# D1MiniTerminalBoard2Sided.net
KiCad netlist of a schematic drawn in EAGLE
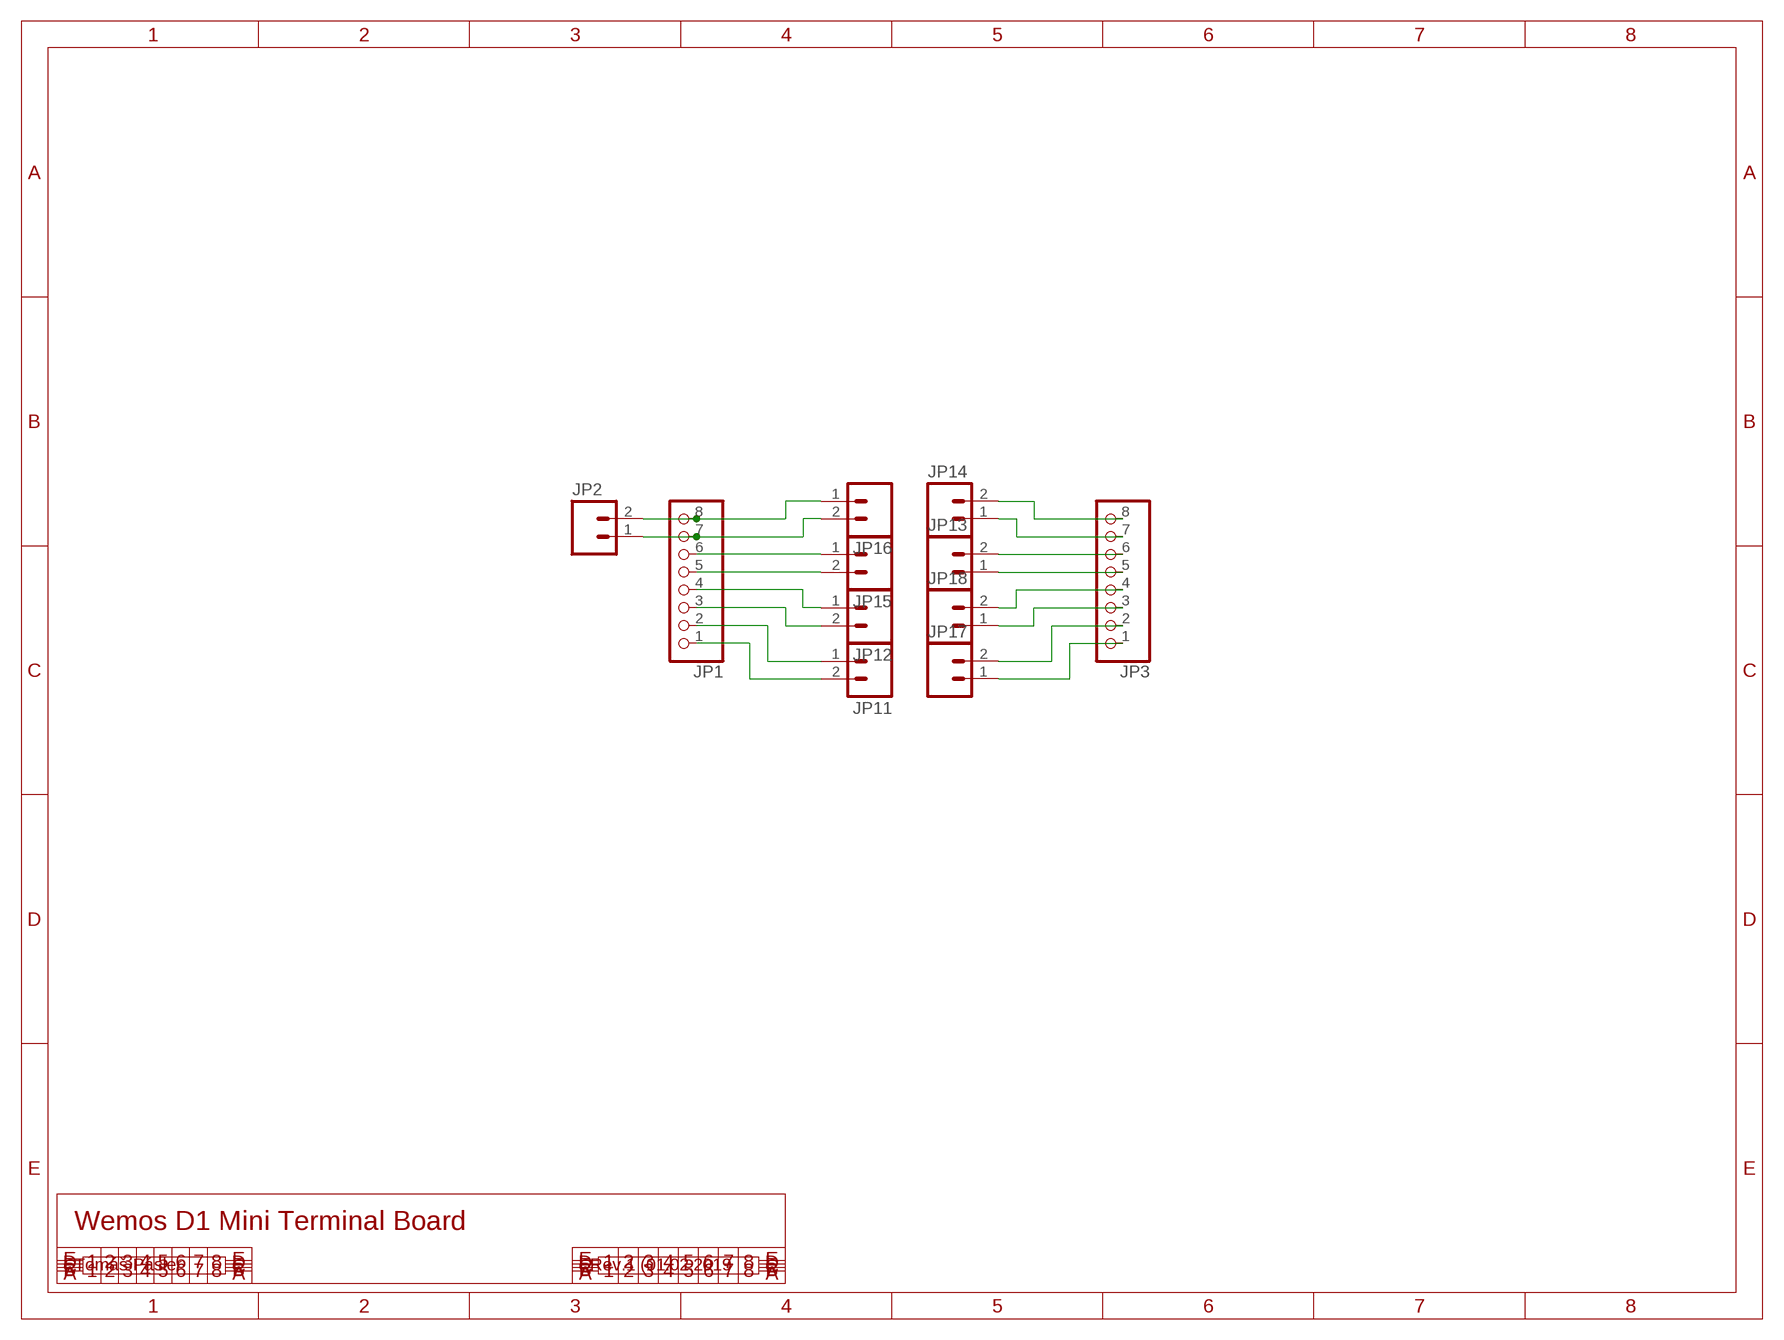
[diagram p0: schematic, sheet 1]

(export (version "E")
  (design (tool "Eeschema 10.0.6"))
  (components
    (comp (ref "JP1")
      (value "PINHD-1X8")
      (footprint "eagle-import:1X08")
      (libsource (lib "eagle-import") (part "PINHD-1X8"))
    )
    (comp (ref "JP2")
      (value "M023.5MM")
      (footprint "eagle-import:SCREWTERMINAL-3.5MM-2")
      (libsource (lib "eagle-import") (part "M023.5MM"))
    )
    (comp (ref "JP3")
      (value "PINHD-1X8")
      (footprint "eagle-import:1X08")
      (libsource (lib "eagle-import") (part "PINHD-1X8"))
    )
    (comp (ref "JP11")
      (value "M023.5MM")
      (footprint "eagle-import:SCREWTERMINAL-3.5MM-2")
      (libsource (lib "eagle-import") (part "M023.5MM"))
    )
    (comp (ref "JP12")
      (value "M023.5MM")
      (footprint "eagle-import:SCREWTERMINAL-3.5MM-2")
      (libsource (lib "eagle-import") (part "M023.5MM"))
    )
    (comp (ref "JP13")
      (value "M023.5MM")
      (footprint "eagle-import:SCREWTERMINAL-3.5MM-2")
      (libsource (lib "eagle-import") (part "M023.5MM"))
    )
    (comp (ref "JP14")
      (value "M023.5MM")
      (footprint "eagle-import:SCREWTERMINAL-3.5MM-2")
      (libsource (lib "eagle-import") (part "M023.5MM"))
    )
    (comp (ref "JP15")
      (value "M023.5MM")
      (footprint "eagle-import:SCREWTERMINAL-3.5MM-2")
      (libsource (lib "eagle-import") (part "M023.5MM"))
    )
    (comp (ref "JP16")
      (value "M023.5MM")
      (footprint "eagle-import:SCREWTERMINAL-3.5MM-2")
      (libsource (lib "eagle-import") (part "M023.5MM"))
    )
    (comp (ref "JP17")
      (value "M023.5MM")
      (footprint "eagle-import:SCREWTERMINAL-3.5MM-2")
      (libsource (lib "eagle-import") (part "M023.5MM"))
    )
    (comp (ref "JP18")
      (value "M023.5MM")
      (footprint "eagle-import:SCREWTERMINAL-3.5MM-2")
      (libsource (lib "eagle-import") (part "M023.5MM"))
    )
  )
  (nets
    (net (code "1") (name "Net-(JP1-Pad1)") (class "Default")
      (node (ref "JP1") (pin "1") (pinfunction "1_1") (pintype "passive"))
      (node (ref "JP11") (pin "2") (pinfunction "2_2") (pintype "passive"))
    )
    (net (code "2") (name "Net-(JP1-Pad2)") (class "Default")
      (node (ref "JP1") (pin "2") (pinfunction "2_2") (pintype "passive"))
      (node (ref "JP11") (pin "1") (pinfunction "1_1") (pintype "passive"))
    )
    (net (code "3") (name "Net-(JP1-Pad3)") (class "Default")
      (node (ref "JP1") (pin "3") (pinfunction "3_3") (pintype "passive"))
      (node (ref "JP12") (pin "2") (pinfunction "2_2") (pintype "passive"))
    )
    (net (code "4") (name "Net-(JP1-Pad4)") (class "Default")
      (node (ref "JP1") (pin "4") (pinfunction "4_4") (pintype "passive"))
      (node (ref "JP12") (pin "1") (pinfunction "1_1") (pintype "passive"))
    )
    (net (code "5") (name "Net-(JP1-Pad5)") (class "Default")
      (node (ref "JP1") (pin "5") (pinfunction "5_5") (pintype "passive"))
      (node (ref "JP15") (pin "2") (pinfunction "2_2") (pintype "passive"))
    )
    (net (code "6") (name "Net-(JP1-Pad6)") (class "Default")
      (node (ref "JP1") (pin "6") (pinfunction "6_6") (pintype "passive"))
      (node (ref "JP15") (pin "1") (pinfunction "1_1") (pintype "passive"))
    )
    (net (code "7") (name "Net-(JP1-Pad7)") (class "Default")
      (node (ref "JP1") (pin "7") (pinfunction "7_7") (pintype "passive"))
      (node (ref "JP16") (pin "2") (pinfunction "2_2") (pintype "passive"))
      (node (ref "JP2") (pin "1") (pinfunction "1_1") (pintype "passive"))
    )
    (net (code "8") (name "Net-(JP1-Pad8)") (class "Default")
      (node (ref "JP1") (pin "8") (pinfunction "8_8") (pintype "passive"))
      (node (ref "JP16") (pin "1") (pinfunction "1_1") (pintype "passive"))
      (node (ref "JP2") (pin "2") (pinfunction "2_2") (pintype "passive"))
    )
    (net (code "9") (name "Net-(JP13-Pad1)") (class "Default")
      (node (ref "JP13") (pin "1") (pinfunction "1_1") (pintype "passive"))
      (node (ref "JP3") (pin "5") (pinfunction "5_5") (pintype "passive"))
    )
    (net (code "10") (name "Net-(JP13-Pad2)") (class "Default")
      (node (ref "JP13") (pin "2") (pinfunction "2_2") (pintype "passive"))
      (node (ref "JP3") (pin "6") (pinfunction "6_6") (pintype "passive"))
    )
    (net (code "11") (name "Net-(JP14-Pad1)") (class "Default")
      (node (ref "JP14") (pin "1") (pinfunction "1_1") (pintype "passive"))
      (node (ref "JP3") (pin "7") (pinfunction "7_7") (pintype "passive"))
    )
    (net (code "12") (name "Net-(JP14-Pad2)") (class "Default")
      (node (ref "JP14") (pin "2") (pinfunction "2_2") (pintype "passive"))
      (node (ref "JP3") (pin "8") (pinfunction "8_8") (pintype "passive"))
    )
    (net (code "13") (name "Net-(JP17-Pad1)") (class "Default")
      (node (ref "JP17") (pin "1") (pinfunction "1_1") (pintype "passive"))
      (node (ref "JP3") (pin "1") (pinfunction "1_1") (pintype "passive"))
    )
    (net (code "14") (name "Net-(JP17-Pad2)") (class "Default")
      (node (ref "JP17") (pin "2") (pinfunction "2_2") (pintype "passive"))
      (node (ref "JP3") (pin "2") (pinfunction "2_2") (pintype "passive"))
    )
    (net (code "15") (name "Net-(JP18-Pad1)") (class "Default")
      (node (ref "JP18") (pin "1") (pinfunction "1_1") (pintype "passive"))
      (node (ref "JP3") (pin "3") (pinfunction "3_3") (pintype "passive"))
    )
    (net (code "16") (name "Net-(JP18-Pad2)") (class "Default")
      (node (ref "JP18") (pin "2") (pinfunction "2_2") (pintype "passive"))
      (node (ref "JP3") (pin "4") (pinfunction "4_4") (pintype "passive"))
    )
  )
)
